# Main.net
KiCad netlist of a schematic drawn in Altium Designer
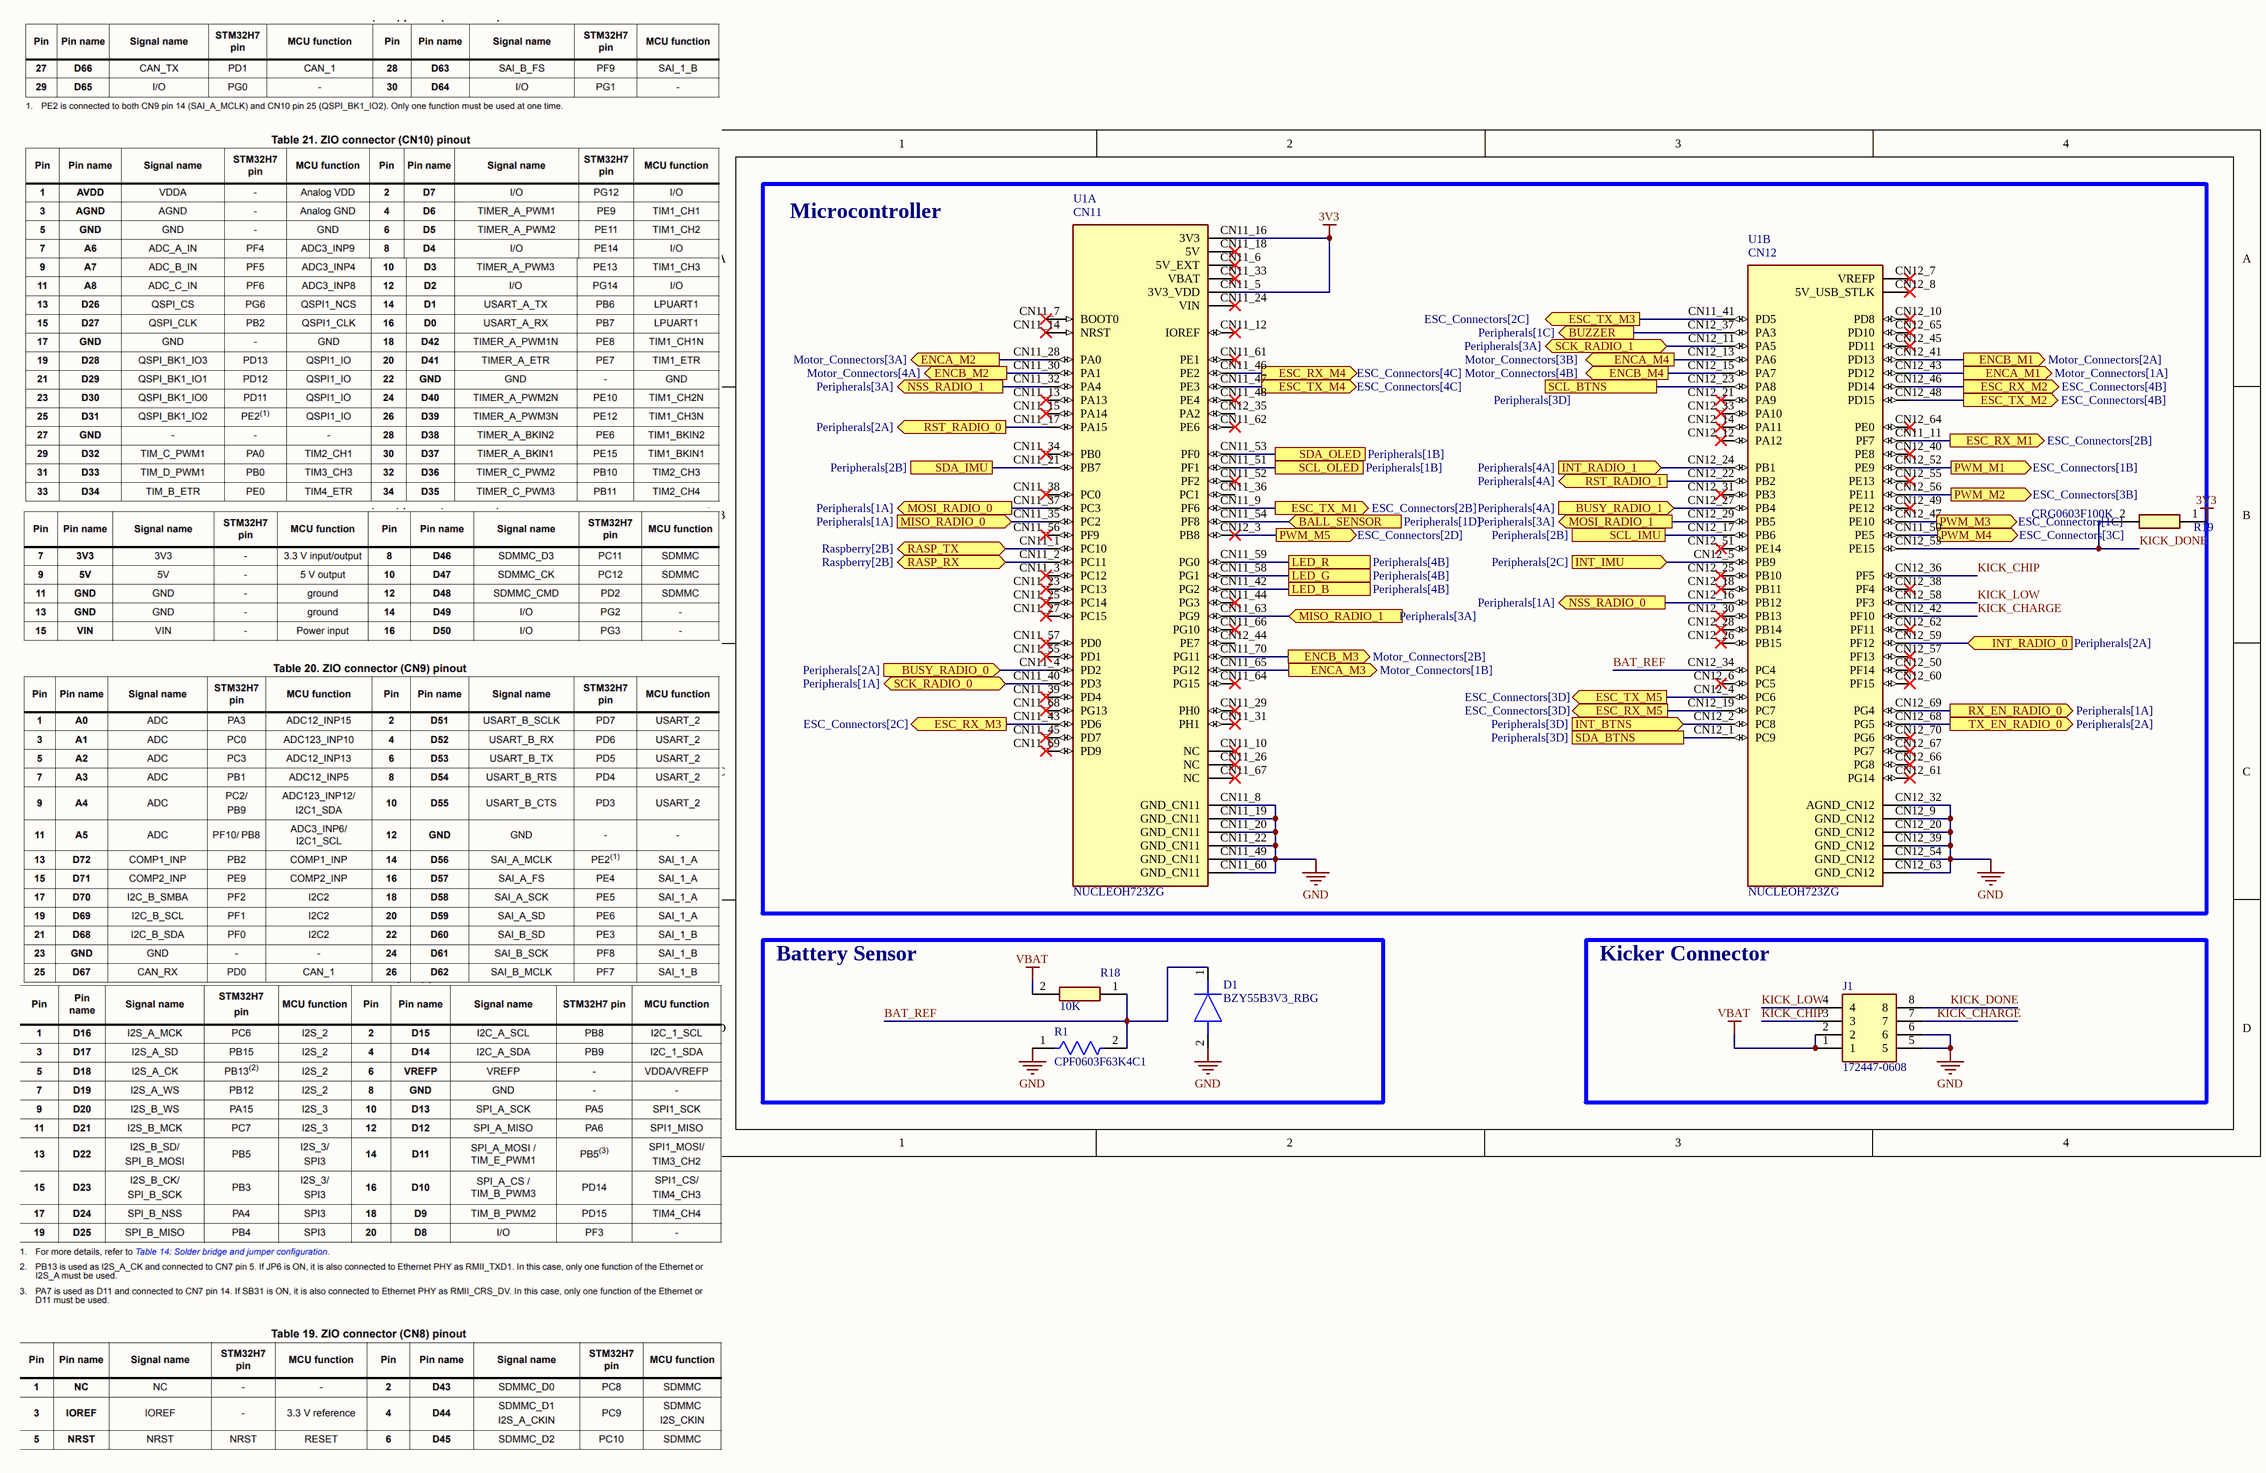
[diagram p0: Main.SchDoc]

(export (version "E")
  (design (tool "Eeschema 10.0.6"))
  (components
    (comp (ref "D1")
      (value "BZY55B3V3_RBG")
      (footprint "roboime:BZY55B3V3RBG")
      (description "Diode")
      (fields
        (field (name "MANUFACTURER_PART_NUMBER") "BZY55B3V3 RBG")
        (field (name "MOUSER PART NUMBER") "821-BZY55B3V3RBG")
      )
      (libsource (lib "roboime") (part "BZY55B3V3_RBG"))
    )
    (comp (ref "J1")
      (value "172447-0608")
      (footprint "roboime:172447-YY08")
      (description "Connector")
      (fields (field (name "MOUSER PART NUMBER") "538-172447-0608"))
      (libsource (lib "roboime") (part "172447-0608"))
    )
    (comp (ref "R1")
      (value "CPF0603F63K4C1")
      (footprint "FP-CPF0603-MFG")
      (description "RES SMD 63.4KΩ 1% 1/16W 0603")
      (fields
        (field (name "OCTOPART") "https://octopart.com/cpf0603f63k4c1-te+connectivity-7515022")
        (field (name "TOLERANCE") "1%")
      )
      (libsource (lib "Altium Content Vault") (part "1029c3af85768c4190bb7ad29bc67b5"))
    )
    (comp (ref "R18")
      (value "10K")
      (footprint "roboime:RESC1608X55N")
      (description "Resistor")
      (fields
        (field (name "MANUFACTURER_PART_NUMBER") "ERJ-U3RD1002V")
        (field (name "MOUSER PART NUMBER") "667-ERJ-U3RD1002V")
      )
      (libsource (lib "roboime") (part "ERJ-U3RD1002V"))
    )
    (comp (ref "R19")
      (value "CRG0603F100K")
      (footprint "roboime:RESC1608X55N")
      (description "Resistor")
      (fields (field (name "MOUSER PART NUMBER") "279-CRG0603F100K"))
      (libsource (lib "roboime") (part "CRG0603F100K"))
    )
    (comp (ref "U1")
      (value "NUCLEOH723ZG")
      (footprint "roboime:NEW_NUCLEO")
      (description "STM32H723ZG Nucleo-144 STM32H7 STM32 MCU 32-Bit Embedded Evaluation Board")
      (fields (field (name "MF") "STMicroelectronics"))
      (libsource (lib "") (part "NUCLEOH723ZG_1"))
    )
  )
  (nets
    (net (code "2") (name "/BALL_SENSOR") (class "Default")
      (node (ref "U1") (pin "CN11_54") (pinfunction "PF8_CN11_54") (pintype "bidirectional"))
    )
    (net (code "3") (name "/BAT_REF") (class "Default")
      (node (ref "D1") (pin "1") (pinfunction "K_1") (pintype "passive"))
      (node (ref "R1") (pin "2") (pinfunction "2_2") (pintype "passive"))
      (node (ref "R18") (pin "1") (pinfunction "1_1") (pintype "passive"))
      (node (ref "U1") (pin "CN12_34") (pinfunction "PC4_CN12_34") (pintype "bidirectional"))
    )
    (net (code "4") (name "/BUSY_RADIO_0") (class "Default")
      (node (ref "U1") (pin "CN11_4") (pinfunction "PD2_CN11_4") (pintype "bidirectional"))
    )
    (net (code "5") (name "/BUSY_RADIO_1") (class "Default")
      (node (ref "U1") (pin "CN12_27") (pinfunction "PB4_CN12_27") (pintype "bidirectional"))
    )
    (net (code "6") (name "/BUZZER") (class "Default")
      (node (ref "U1") (pin "CN12_37") (pinfunction "PA3_CN12_37") (pintype "bidirectional"))
    )
    (net (code "7") (name "/ENCA_M1") (class "Default")
      (node (ref "U1") (pin "CN12_43") (pinfunction "PD12_CN12_43") (pintype "bidirectional"))
    )
    (net (code "8") (name "/ENCA_M2") (class "Default")
      (node (ref "U1") (pin "CN11_28") (pinfunction "PA0_CN11_28") (pintype "bidirectional"))
    )
    (net (code "9") (name "/ENCA_M3") (class "Default")
      (node (ref "U1") (pin "CN11_65") (pinfunction "PG12_CN11_65") (pintype "bidirectional"))
    )
    (net (code "10") (name "/ENCA_M4") (class "Default")
      (node (ref "U1") (pin "CN12_13") (pinfunction "PA6_CN12_13") (pintype "bidirectional"))
    )
    (net (code "11") (name "/ENCB_M1") (class "Default")
      (node (ref "U1") (pin "CN12_41") (pinfunction "PD13_CN12_41") (pintype "bidirectional"))
    )
    (net (code "12") (name "/ENCB_M2") (class "Default")
      (node (ref "U1") (pin "CN11_30") (pinfunction "PA1_CN11_30") (pintype "bidirectional"))
    )
    (net (code "13") (name "/ENCB_M3") (class "Default")
      (node (ref "U1") (pin "CN11_70") (pinfunction "PG11_CN11_70") (pintype "bidirectional"))
    )
    (net (code "14") (name "/ENCB_M4") (class "Default")
      (node (ref "U1") (pin "CN12_15") (pinfunction "PA7_CN12_15") (pintype "bidirectional"))
    )
    (net (code "15") (name "/ESC_RX_M1") (class "Default")
      (node (ref "U1") (pin "CN11_11") (pinfunction "PF7_CN11_11") (pintype "bidirectional"))
    )
    (net (code "16") (name "/ESC_RX_M2") (class "Default")
      (node (ref "U1") (pin "CN12_46") (pinfunction "PD14_CN12_46") (pintype "bidirectional"))
    )
    (net (code "17") (name "/ESC_RX_M3") (class "Default")
      (node (ref "U1") (pin "CN11_43") (pinfunction "PD6_CN11_43") (pintype "bidirectional"))
    )
    (net (code "18") (name "/ESC_RX_M4") (class "Default")
      (node (ref "U1") (pin "CN11_46") (pinfunction "PE2_CN11_46") (pintype "bidirectional"))
    )
    (net (code "19") (name "/ESC_RX_M5") (class "Default")
      (node (ref "U1") (pin "CN12_19") (pinfunction "PC7_CN12_19") (pintype "bidirectional"))
    )
    (net (code "20") (name "/ESC_TX_M1") (class "Default")
      (node (ref "U1") (pin "CN11_9") (pinfunction "PF6_CN11_9") (pintype "bidirectional"))
    )
    (net (code "21") (name "/ESC_TX_M2") (class "Default")
      (node (ref "U1") (pin "CN12_48") (pinfunction "PD15_CN12_48") (pintype "bidirectional"))
    )
    (net (code "22") (name "/ESC_TX_M3") (class "Default")
      (node (ref "U1") (pin "CN11_41") (pinfunction "PD5_CN11_41") (pintype "bidirectional"))
    )
    (net (code "23") (name "/ESC_TX_M4") (class "Default")
      (node (ref "U1") (pin "CN11_47") (pinfunction "PE3_CN11_47") (pintype "bidirectional"))
    )
    (net (code "24") (name "/ESC_TX_M5") (class "Default")
      (node (ref "U1") (pin "CN12_4") (pinfunction "PC6_CN12_4") (pintype "bidirectional"))
    )
    (net (code "25") (name "/INT_BTNS") (class "Default")
      (node (ref "U1") (pin "CN12_2") (pinfunction "PC8_CN12_2") (pintype "bidirectional"))
    )
    (net (code "26") (name "/INT_IMU") (class "Default")
      (node (ref "U1") (pin "CN12_5") (pinfunction "PB9_CN12_5") (pintype "bidirectional"))
    )
    (net (code "27") (name "/INT_RADIO_0") (class "Default")
      (node (ref "U1") (pin "CN12_59") (pinfunction "PF12_CN12_59") (pintype "bidirectional"))
    )
    (net (code "28") (name "/INT_RADIO_1") (class "Default")
      (node (ref "U1") (pin "CN12_24") (pinfunction "PB1_CN12_24") (pintype "bidirectional"))
    )
    (net (code "29") (name "/KICK_CHARGE") (class "Default")
      (node (ref "J1") (pin "7") (pinfunction "7_7") (pintype "passive"))
      (node (ref "U1") (pin "CN12_42") (pinfunction "PF10_CN12_42") (pintype "bidirectional"))
    )
    (net (code "30") (name "/KICK_CHIP") (class "Default")
      (node (ref "J1") (pin "3") (pinfunction "3_3") (pintype "passive"))
      (node (ref "U1") (pin "CN12_36") (pinfunction "PF5_CN12_36") (pintype "bidirectional"))
    )
    (net (code "31") (name "/KICK_DONE") (class "Default")
      (node (ref "J1") (pin "8") (pinfunction "8_8") (pintype "passive"))
      (node (ref "R19") (pin "2") (pinfunction "2_2") (pintype "passive"))
      (node (ref "U1") (pin "CN12_53") (pinfunction "PE15_CN12_53") (pintype "bidirectional"))
    )
    (net (code "32") (name "/KICK_LOW") (class "Default")
      (node (ref "J1") (pin "4") (pinfunction "4_4") (pintype "passive"))
      (node (ref "U1") (pin "CN12_58") (pinfunction "PF3_CN12_58") (pintype "bidirectional"))
    )
    (net (code "33") (name "/LED_B") (class "Default")
      (node (ref "U1") (pin "CN11_42") (pinfunction "PG2_CN11_42") (pintype "bidirectional"))
    )
    (net (code "34") (name "/LED_G") (class "Default")
      (node (ref "U1") (pin "CN11_58") (pinfunction "PG1_CN11_58") (pintype "bidirectional"))
    )
    (net (code "35") (name "/LED_R") (class "Default")
      (node (ref "U1") (pin "CN11_59") (pinfunction "PG0_CN11_59") (pintype "bidirectional"))
    )
    (net (code "36") (name "/MISO_RADIO_0") (class "Default")
      (node (ref "U1") (pin "CN11_35") (pinfunction "PC2_CN11_35") (pintype "bidirectional"))
    )
    (net (code "37") (name "/MISO_RADIO_1") (class "Default")
      (node (ref "U1") (pin "CN11_63") (pinfunction "PG9_CN11_63") (pintype "bidirectional"))
    )
    (net (code "38") (name "/MOSI_RADIO_0") (class "Default")
      (node (ref "U1") (pin "CN11_37") (pinfunction "PC3_CN11_37") (pintype "bidirectional"))
    )
    (net (code "39") (name "/MOSI_RADIO_1") (class "Default")
      (node (ref "U1") (pin "CN12_29") (pinfunction "PB5_CN12_29") (pintype "bidirectional"))
    )
    (net (code "40") (name "/NSS_RADIO_0") (class "Default")
      (node (ref "U1") (pin "CN12_16") (pinfunction "PB12_CN12_16") (pintype "bidirectional"))
    )
    (net (code "41") (name "/NSS_RADIO_1") (class "Default")
      (node (ref "U1") (pin "CN11_32") (pinfunction "PA4_CN11_32") (pintype "bidirectional"))
    )
    (net (code "42") (name "/PWM_M1") (class "Default")
      (node (ref "U1") (pin "CN12_52") (pinfunction "PE9_CN12_52") (pintype "bidirectional"))
    )
    (net (code "43") (name "/PWM_M2") (class "Default")
      (node (ref "U1") (pin "CN12_56") (pinfunction "PE11_CN12_56") (pintype "bidirectional"))
    )
    (net (code "44") (name "/PWM_M3") (class "Default")
      (node (ref "U1") (pin "CN12_47") (pinfunction "PE10_CN12_47") (pintype "bidirectional"))
    )
    (net (code "45") (name "/PWM_M4") (class "Default")
      (node (ref "U1") (pin "CN11_50") (pinfunction "PE5_CN11_50") (pintype "bidirectional"))
    )
    (net (code "46") (name "/PWM_M5") (class "Default")
      (node (ref "U1") (pin "CN12_3") (pinfunction "PB8_CN12_3") (pintype "bidirectional+no_connect"))
    )
    (net (code "47") (name "/RASP_RX") (class "Default")
      (node (ref "U1") (pin "CN11_2") (pinfunction "PC11_CN11_2") (pintype "bidirectional"))
    )
    (net (code "48") (name "/RASP_TX") (class "Default")
      (node (ref "U1") (pin "CN11_1") (pinfunction "PC10_CN11_1") (pintype "bidirectional"))
    )
    (net (code "49") (name "/RST_RADIO_0") (class "Default")
      (node (ref "U1") (pin "CN11_17") (pinfunction "PA15_CN11_17") (pintype "bidirectional"))
    )
    (net (code "50") (name "/RST_RADIO_1") (class "Default")
      (node (ref "U1") (pin "CN12_22") (pinfunction "PB2_CN12_22") (pintype "bidirectional"))
    )
    (net (code "51") (name "/RX_EN_RADIO_0") (class "Default")
      (node (ref "U1") (pin "CN12_69") (pinfunction "PG4_CN12_69") (pintype "bidirectional"))
    )
    (net (code "52") (name "/SCK_RADIO_0") (class "Default")
      (node (ref "U1") (pin "CN11_40") (pinfunction "PD3_CN11_40") (pintype "bidirectional"))
    )
    (net (code "53") (name "/SCK_RADIO_1") (class "Default")
      (node (ref "U1") (pin "CN12_11") (pinfunction "PA5_CN12_11") (pintype "bidirectional"))
    )
    (net (code "54") (name "/SCL_BTNS") (class "Default")
      (node (ref "U1") (pin "CN12_23") (pinfunction "PA8_CN12_23") (pintype "bidirectional"))
    )
    (net (code "55") (name "/SCL_IMU") (class "Default")
      (node (ref "U1") (pin "CN12_17") (pinfunction "PB6_CN12_17") (pintype "bidirectional"))
    )
    (net (code "56") (name "/SCL_OLED") (class "Default")
      (node (ref "U1") (pin "CN11_51") (pinfunction "PF1_CN11_51") (pintype "bidirectional"))
    )
    (net (code "57") (name "/SDA_BTNS") (class "Default")
      (node (ref "U1") (pin "CN12_1") (pinfunction "PC9_CN12_1") (pintype "bidirectional"))
    )
    (net (code "58") (name "/SDA_IMU") (class "Default")
      (node (ref "U1") (pin "CN11_21") (pinfunction "PB7_CN11_21") (pintype "bidirectional"))
    )
    (net (code "59") (name "/SDA_OLED") (class "Default")
      (node (ref "U1") (pin "CN11_53") (pinfunction "PF0_CN11_53") (pintype "bidirectional"))
    )
    (net (code "60") (name "/TX_EN_RADIO_0") (class "Default")
      (node (ref "U1") (pin "CN12_68") (pinfunction "PG5_CN12_68") (pintype "bidirectional"))
    )
    (net (code "61") (name "3V3") (class "Default")
      (node (ref "R19") (pin "1") (pinfunction "1_1") (pintype "passive"))
      (node (ref "U1") (pin "CN11_16") (pinfunction "3V3_CN11_16") (pintype "power_in"))
      (node (ref "U1") (pin "CN11_5") (pinfunction "3V3_VDD_CN11_5") (pintype "power_in"))
    )
    (net (code "62") (name "GND") (class "Default")
      (node (ref "D1") (pin "2") (pinfunction "A_2") (pintype "passive"))
      (node (ref "J1") (pin "5") (pinfunction "5_5") (pintype "passive"))
      (node (ref "J1") (pin "6") (pinfunction "6_6") (pintype "passive"))
      (node (ref "R1") (pin "1") (pinfunction "1_1") (pintype "passive"))
      (node (ref "U1") (pin "CN11_19") (pinfunction "GND_CN11_CN11_19") (pintype "power_in"))
      (node (ref "U1") (pin "CN11_20") (pinfunction "GND_CN11_CN11_20") (pintype "power_in"))
      (node (ref "U1") (pin "CN11_22") (pinfunction "GND_CN11_CN11_22") (pintype "power_in"))
      (node (ref "U1") (pin "CN11_49") (pinfunction "GND_CN11_CN11_49") (pintype "power_in"))
      (node (ref "U1") (pin "CN11_60") (pinfunction "GND_CN11_CN11_60") (pintype "power_in"))
      (node (ref "U1") (pin "CN11_8") (pinfunction "GND_CN11_CN11_8") (pintype "power_in"))
      (node (ref "U1") (pin "CN12_20") (pinfunction "GND_CN12_CN12_20") (pintype "power_in"))
      (node (ref "U1") (pin "CN12_32") (pinfunction "AGND_CN12_CN12_32") (pintype "power_in"))
      (node (ref "U1") (pin "CN12_39") (pinfunction "GND_CN12_CN12_39") (pintype "power_in"))
      (node (ref "U1") (pin "CN12_54") (pinfunction "GND_CN12_CN12_54") (pintype "power_in"))
      (node (ref "U1") (pin "CN12_63") (pinfunction "GND_CN12_CN12_63") (pintype "power_in"))
      (node (ref "U1") (pin "CN12_9") (pinfunction "GND_CN12_CN12_9") (pintype "power_in"))
    )
    (net (code "63") (name "VBAT") (class "Default")
      (node (ref "J1") (pin "1") (pinfunction "1_1") (pintype "passive"))
      (node (ref "J1") (pin "2") (pinfunction "2_2") (pintype "passive"))
      (node (ref "R18") (pin "2") (pinfunction "2_2") (pintype "passive"))
    )
    (net (code "64") (name "unconnected-(U1A-5V-PadCN11_18)") (class "Default")
      (node (ref "U1") (pin "CN11_18") (pinfunction "5V_CN11_18") (pintype "power_in+no_connect"))
    )
    (net (code "65") (name "unconnected-(U1A-5V_EXT-PadCN11_6)") (class "Default")
      (node (ref "U1") (pin "CN11_6") (pinfunction "5V_EXT_CN11_6") (pintype "power_in+no_connect"))
    )
    (net (code "66") (name "unconnected-(U1A-BOOT0-PadCN11_7)") (class "Default")
      (node (ref "U1") (pin "CN11_7") (pinfunction "BOOT0_CN11_7") (pintype "input+no_connect"))
    )
    (net (code "67") (name "unconnected-(U1A-IOREF-PadCN11_12)") (class "Default")
      (node (ref "U1") (pin "CN11_12") (pinfunction "IOREF_CN11_12") (pintype "bidirectional+no_connect"))
    )
    (net (code "68") (name "unconnected-(U1A-NC-PadCN11_10)") (class "Default")
      (node (ref "U1") (pin "CN11_10") (pinfunction "NC_CN11_10") (pintype "passive+no_connect"))
    )
    (net (code "69") (name "unconnected-(U1A-NC-PadCN11_26)") (class "Default")
      (node (ref "U1") (pin "CN11_26") (pinfunction "NC_CN11_26") (pintype "passive+no_connect"))
    )
    (net (code "70") (name "unconnected-(U1A-NC-PadCN11_67)") (class "Default")
      (node (ref "U1") (pin "CN11_67") (pinfunction "NC_CN11_67") (pintype "passive+no_connect"))
    )
    (net (code "71") (name "unconnected-(U1A-NRST-PadCN11_14)") (class "Default")
      (node (ref "U1") (pin "CN11_14") (pinfunction "NRST_CN11_14") (pintype "input+no_connect"))
    )
    (net (code "72") (name "unconnected-(U1A-PA2-PadCN12_35)") (class "Default")
      (node (ref "U1") (pin "CN12_35") (pinfunction "PA2_CN12_35") (pintype "bidirectional"))
    )
    (net (code "73") (name "unconnected-(U1A-PA13-PadCN11_13)") (class "Default")
      (node (ref "U1") (pin "CN11_13") (pinfunction "PA13_CN11_13") (pintype "bidirectional+no_connect"))
    )
    (net (code "74") (name "unconnected-(U1A-PA14-PadCN11_15)") (class "Default")
      (node (ref "U1") (pin "CN11_15") (pinfunction "PA14_CN11_15") (pintype "bidirectional+no_connect"))
    )
    (net (code "75") (name "unconnected-(U1A-PB0-PadCN11_34)") (class "Default")
      (node (ref "U1") (pin "CN11_34") (pinfunction "PB0_CN11_34") (pintype "bidirectional+no_connect"))
    )
    (net (code "76") (name "unconnected-(U1A-PC0-PadCN11_38)") (class "Default")
      (node (ref "U1") (pin "CN11_38") (pinfunction "PC0_CN11_38") (pintype "bidirectional+no_connect"))
    )
    (net (code "77") (name "unconnected-(U1A-PC1-PadCN11_36)") (class "Default")
      (node (ref "U1") (pin "CN11_36") (pinfunction "PC1_CN11_36") (pintype "bidirectional"))
    )
    (net (code "78") (name "unconnected-(U1A-PC12-PadCN11_3)") (class "Default")
      (node (ref "U1") (pin "CN11_3") (pinfunction "PC12_CN11_3") (pintype "bidirectional+no_connect"))
    )
    (net (code "79") (name "unconnected-(U1A-PC13-PadCN11_23)") (class "Default")
      (node (ref "U1") (pin "CN11_23") (pinfunction "PC13_CN11_23") (pintype "bidirectional+no_connect"))
    )
    (net (code "80") (name "unconnected-(U1A-PC14-PadCN11_25)") (class "Default")
      (node (ref "U1") (pin "CN11_25") (pinfunction "PC14_CN11_25") (pintype "bidirectional+no_connect"))
    )
    (net (code "81") (name "unconnected-(U1A-PC15-PadCN11_27)") (class "Default")
      (node (ref "U1") (pin "CN11_27") (pinfunction "PC15_CN11_27") (pintype "bidirectional+no_connect"))
    )
    (net (code "82") (name "unconnected-(U1A-PD0-PadCN11_57)") (class "Default")
      (node (ref "U1") (pin "CN11_57") (pinfunction "PD0_CN11_57") (pintype "bidirectional+no_connect"))
    )
    (net (code "83") (name "unconnected-(U1A-PD1-PadCN11_55)") (class "Default")
      (node (ref "U1") (pin "CN11_55") (pinfunction "PD1_CN11_55") (pintype "bidirectional+no_connect"))
    )
    (net (code "84") (name "unconnected-(U1A-PD4-PadCN11_39)") (class "Default")
      (node (ref "U1") (pin "CN11_39") (pinfunction "PD4_CN11_39") (pintype "bidirectional+no_connect"))
    )
    (net (code "85") (name "unconnected-(U1A-PD7-PadCN11_45)") (class "Default")
      (node (ref "U1") (pin "CN11_45") (pinfunction "PD7_CN11_45") (pintype "bidirectional+no_connect"))
    )
    (net (code "86") (name "unconnected-(U1A-PD9-PadCN11_69)") (class "Default")
      (node (ref "U1") (pin "CN11_69") (pinfunction "PD9_CN11_69") (pintype "bidirectional+no_connect"))
    )
    (net (code "87") (name "unconnected-(U1A-PE1-PadCN11_61)") (class "Default")
      (node (ref "U1") (pin "CN11_61") (pinfunction "PE1_CN11_61") (pintype "bidirectional+no_connect"))
    )
    (net (code "88") (name "unconnected-(U1A-PE4-PadCN11_48)") (class "Default")
      (node (ref "U1") (pin "CN11_48") (pinfunction "PE4_CN11_48") (pintype "bidirectional+no_connect"))
    )
    (net (code "89") (name "unconnected-(U1A-PE6-PadCN11_62)") (class "Default")
      (node (ref "U1") (pin "CN11_62") (pinfunction "PE6_CN11_62") (pintype "bidirectional+no_connect"))
    )
    (net (code "90") (name "unconnected-(U1A-PE7-PadCN12_44)") (class "Default")
      (node (ref "U1") (pin "CN12_44") (pinfunction "PE7_CN12_44") (pintype "bidirectional"))
    )
    (net (code "91") (name "unconnected-(U1A-PF2-PadCN11_52)") (class "Default")
      (node (ref "U1") (pin "CN11_52") (pinfunction "PF2_CN11_52") (pintype "bidirectional+no_connect"))
    )
    (net (code "92") (name "unconnected-(U1A-PF9-PadCN11_56)") (class "Default")
      (node (ref "U1") (pin "CN11_56") (pinfunction "PF9_CN11_56") (pintype "bidirectional+no_connect"))
    )
    (net (code "93") (name "unconnected-(U1A-PG3-PadCN11_44)") (class "Default")
      (node (ref "U1") (pin "CN11_44") (pinfunction "PG3_CN11_44") (pintype "bidirectional+no_connect"))
    )
    (net (code "94") (name "unconnected-(U1A-PG10-PadCN11_66)") (class "Default")
      (node (ref "U1") (pin "CN11_66") (pinfunction "PG10_CN11_66") (pintype "bidirectional+no_connect"))
    )
    (net (code "95") (name "unconnected-(U1A-PG13-PadCN11_68)") (class "Default")
      (node (ref "U1") (pin "CN11_68") (pinfunction "PG13_CN11_68") (pintype "bidirectional+no_connect"))
    )
    (net (code "96") (name "unconnected-(U1A-PG15-PadCN11_64)") (class "Default")
      (node (ref "U1") (pin "CN11_64") (pinfunction "PG15_CN11_64") (pintype "bidirectional+no_connect"))
    )
    (net (code "97") (name "unconnected-(U1A-PH0-PadCN11_29)") (class "Default")
      (node (ref "U1") (pin "CN11_29") (pinfunction "PH0_CN11_29") (pintype "bidirectional+no_connect"))
    )
    (net (code "98") (name "unconnected-(U1A-PH1-PadCN11_31)") (class "Default")
      (node (ref "U1") (pin "CN11_31") (pinfunction "PH1_CN11_31") (pintype "bidirectional+no_connect"))
    )
    (net (code "99") (name "unconnected-(U1A-VBAT-PadCN11_33)") (class "Default")
      (node (ref "U1") (pin "CN11_33") (pinfunction "VBAT_CN11_33") (pintype "power_in+no_connect"))
    )
    (net (code "100") (name "unconnected-(U1A-VIN-PadCN11_24)") (class "Default")
      (node (ref "U1") (pin "CN11_24") (pinfunction "VIN_CN11_24") (pintype "power_in+no_connect"))
    )
    (net (code "101") (name "unconnected-(U1B-5V_USB_STLK-PadCN12_8)") (class "Default")
      (node (ref "U1") (pin "CN12_8") (pinfunction "5V_USB_STLK_CN12_8") (pintype "power_in+no_connect"))
    )
    (net (code "102") (name "unconnected-(U1B-PA9-PadCN12_21)") (class "Default")
      (node (ref "U1") (pin "CN12_21") (pinfunction "PA9_CN12_21") (pintype "bidirectional+no_connect"))
    )
    (net (code "103") (name "unconnected-(U1B-PA10-PadCN12_33)") (class "Default")
      (node (ref "U1") (pin "CN12_33") (pinfunction "PA10_CN12_33") (pintype "bidirectional+no_connect"))
    )
    (net (code "104") (name "unconnected-(U1B-PA11-PadCN12_14)") (class "Default")
      (node (ref "U1") (pin "CN12_14") (pinfunction "PA11_CN12_14") (pintype "bidirectional+no_connect"))
    )
    (net (code "105") (name "unconnected-(U1B-PA12-PadCN12_12)") (class "Default")
      (node (ref "U1") (pin "CN12_12") (pinfunction "PA12_CN12_12") (pintype "bidirectional+no_connect"))
    )
    (net (code "106") (name "unconnected-(U1B-PB3-PadCN12_31)") (class "Default")
      (node (ref "U1") (pin "CN12_31") (pinfunction "PB3_CN12_31") (pintype "bidirectional+no_connect"))
    )
    (net (code "107") (name "unconnected-(U1B-PB10-PadCN12_25)") (class "Default")
      (node (ref "U1") (pin "CN12_25") (pinfunction "PB10_CN12_25") (pintype "bidirectional+no_connect"))
    )
    (net (code "108") (name "unconnected-(U1B-PB11-PadCN12_18)") (class "Default")
      (node (ref "U1") (pin "CN12_18") (pinfunction "PB11_CN12_18") (pintype "bidirectional+no_connect"))
    )
    (net (code "109") (name "unconnected-(U1B-PB13-PadCN12_30)") (class "Default")
      (node (ref "U1") (pin "CN12_30") (pinfunction "PB13_CN12_30") (pintype "bidirectional+no_connect"))
    )
    (net (code "110") (name "unconnected-(U1B-PB14-PadCN12_28)") (class "Default")
      (node (ref "U1") (pin "CN12_28") (pinfunction "PB14_CN12_28") (pintype "bidirectional+no_connect"))
    )
    (net (code "111") (name "unconnected-(U1B-PB15-PadCN12_26)") (class "Default")
      (node (ref "U1") (pin "CN12_26") (pinfunction "PB15_CN12_26") (pintype "bidirectional+no_connect"))
    )
    (net (code "112") (name "unconnected-(U1B-PC5-PadCN12_6)") (class "Default")
      (node (ref "U1") (pin "CN12_6") (pinfunction "PC5_CN12_6") (pintype "bidirectional+no_connect"))
    )
    (net (code "113") (name "unconnected-(U1B-PD8-PadCN12_10)") (class "Default")
      (node (ref "U1") (pin "CN12_10") (pinfunction "PD8_CN12_10") (pintype "bidirectional+no_connect"))
    )
    (net (code "114") (name "unconnected-(U1B-PD10-PadCN12_65)") (class "Default")
      (node (ref "U1") (pin "CN12_65") (pinfunction "PD10_CN12_65") (pintype "bidirectional+no_connect"))
    )
    (net (code "115") (name "unconnected-(U1B-PD11-PadCN12_45)") (class "Default")
      (node (ref "U1") (pin "CN12_45") (pinfunction "PD11_CN12_45") (pintype "bidirectional+no_connect"))
    )
    (net (code "116") (name "unconnected-(U1B-PE0-PadCN12_64)") (class "Default")
      (node (ref "U1") (pin "CN12_64") (pinfunction "PE0_CN12_64") (pintype "bidirectional+no_connect"))
    )
    (net (code "117") (name "unconnected-(U1B-PE8-PadCN12_40)") (class "Default")
      (node (ref "U1") (pin "CN12_40") (pinfunction "PE8_CN12_40") (pintype "bidirectional+no_connect"))
    )
    (net (code "118") (name "unconnected-(U1B-PE12-PadCN12_49)") (class "Default")
      (node (ref "U1") (pin "CN12_49") (pinfunction "PE12_CN12_49") (pintype "bidirectional+no_connect"))
    )
    (net (code "119") (name "unconnected-(U1B-PE13-PadCN12_55)") (class "Default")
      (node (ref "U1") (pin "CN12_55") (pinfunction "PE13_CN12_55") (pintype "bidirectional+no_connect"))
    )
    (net (code "120") (name "unconnected-(U1B-PE14-PadCN12_51)") (class "Default")
      (node (ref "U1") (pin "CN12_51") (pinfunction "PE14_CN12_51") (pintype "bidirectional+no_connect"))
    )
    (net (code "121") (name "unconnected-(U1B-PF4-PadCN12_38)") (class "Default")
      (node (ref "U1") (pin "CN12_38") (pinfunction "PF4_CN12_38") (pintype "bidirectional+no_connect"))
    )
    (net (code "122") (name "unconnected-(U1B-PF11-PadCN12_62)") (class "Default")
      (node (ref "U1") (pin "CN12_62") (pinfunction "PF11_CN12_62") (pintype "bidirectional+no_connect"))
    )
    (net (code "123") (name "unconnected-(U1B-PF13-PadCN12_57)") (class "Default")
      (node (ref "U1") (pin "CN12_57") (pinfunction "PF13_CN12_57") (pintype "bidirectional+no_connect"))
    )
    (net (code "124") (name "unconnected-(U1B-PF14-PadCN12_50)") (class "Default")
      (node (ref "U1") (pin "CN12_50") (pinfunction "PF14_CN12_50") (pintype "bidirectional+no_connect"))
    )
    (net (code "125") (name "unconnected-(U1B-PF15-PadCN12_60)") (class "Default")
      (node (ref "U1") (pin "CN12_60") (pinfunction "PF15_CN12_60") (pintype "bidirectional+no_connect"))
    )
    (net (code "126") (name "unconnected-(U1B-PG6-PadCN12_70)") (class "Default")
      (node (ref "U1") (pin "CN12_70") (pinfunction "PG6_CN12_70") (pintype "bidirectional+no_connect"))
    )
    (net (code "127") (name "unconnected-(U1B-PG7-PadCN12_67)") (class "Default")
      (node (ref "U1") (pin "CN12_67") (pinfunction "PG7_CN12_67") (pintype "bidirectional+no_connect"))
    )
    (net (code "128") (name "unconnected-(U1B-PG8-PadCN12_66)") (class "Default")
      (node (ref "U1") (pin "CN12_66") (pinfunction "PG8_CN12_66") (pintype "bidirectional+no_connect"))
    )
    (net (code "129") (name "unconnected-(U1B-PG14-PadCN12_61)") (class "Default")
      (node (ref "U1") (pin "CN12_61") (pinfunction "PG14_CN12_61") (pintype "bidirectional+no_connect"))
    )
    (net (code "130") (name "unconnected-(U1B-VREFP-PadCN12_7)") (class "Default")
      (node (ref "U1") (pin "CN12_7") (pinfunction "VREFP_CN12_7") (pintype "power_in+no_connect"))
    )
  )
)
